# 50AN_DIGI.net
KiCad netlist of a schematic drawn in Altium Designer
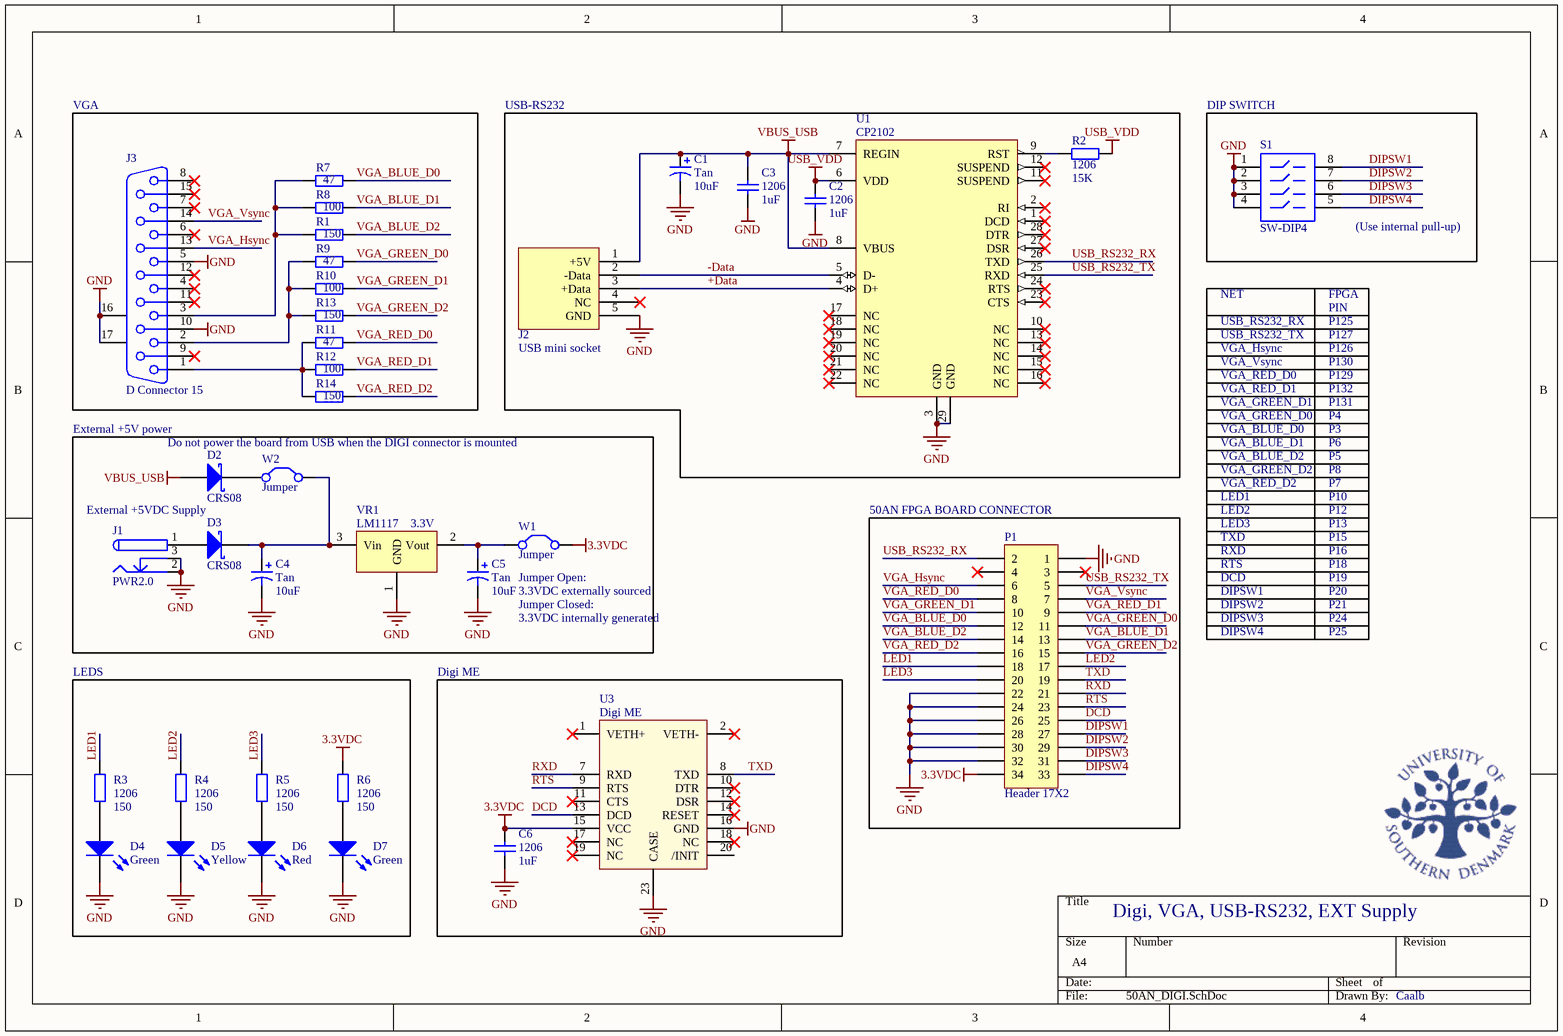
[diagram p0: 50AN_DIGI.SchDoc]

(export (version "E")
  (design (tool "Eeschema 10.0.6"))
  (components
    (comp (ref "C1")
      (value "Tan")
      (footprint "Tantal size A")
      (description "Polarized Capacitor (Radial)")
      (fields (field (name "ALTIUM_VALUE") "10uF") (field (name "PUBLISHER") "Altium Limited"))
      (libsource (lib "Miscellaneous Devices") (part "Cap Pol1"))
    )
    (comp (ref "C2")
      (value "1206")
      (footprint "1206C")
      (description "Capacitor")
      (fields (field (name "ALTIUM_VALUE") "1uF") (field (name "PUBLISHER") "Altium Limited"))
      (libsource (lib "Miscellaneous Devices") (part "Cap"))
    )
    (comp (ref "C3")
      (value "1206")
      (footprint "1206C")
      (description "Capacitor")
      (fields (field (name "ALTIUM_VALUE") "1uF") (field (name "PUBLISHER") "Altium Limited"))
      (libsource (lib "Miscellaneous Devices") (part "Cap"))
    )
    (comp (ref "C4")
      (value "Tan")
      (footprint "Tantal size A")
      (description "Polarized Capacitor (Radial)")
      (fields (field (name "ALTIUM_VALUE") "10uF") (field (name "PUBLISHER") "Altium Limited"))
      (libsource (lib "Miscellaneous Devices") (part "Cap Pol1"))
    )
    (comp (ref "C5")
      (value "Tan")
      (footprint "Tantal size A")
      (description "Polarized Capacitor (Radial)")
      (fields (field (name "ALTIUM_VALUE") "10uF") (field (name "PUBLISHER") "Altium Limited"))
      (libsource (lib "Miscellaneous Devices") (part "Cap Pol1"))
    )
    (comp (ref "C6")
      (value "1206")
      (footprint "1206C")
      (description "Capacitor")
      (fields (field (name "ALTIUM_VALUE") "1uF") (field (name "PUBLISHER") "Altium Limited"))
      (libsource (lib "Miscellaneous Devices") (part "Cap"))
    )
    (comp (ref "D2")
      (value "CRS08")
      (footprint "CRS08")
      (description "Schottky Rectifier")
      (fields (field (name "PUBLISHER") "Altium Limited"))
      (libsource (lib "Miscellaneous Devices") (part "Diode 11DQ03"))
    )
    (comp (ref "D3")
      (value "CRS08")
      (footprint "CRS08")
      (description "Schottky Rectifier")
      (fields (field (name "PUBLISHER") "Altium Limited"))
      (libsource (lib "Miscellaneous Devices") (part "Diode 11DQ03"))
    )
    (comp (ref "D4")
      (value "Green")
      (footprint "LED1206G")
      (fields (field (name "PUBLISHER") "Altium Limited"))
      (libsource (lib "Miscellaneous Devices") (part "LED0"))
    )
    (comp (ref "D5")
      (value "Yellow")
      (footprint "LED1206Y")
      (fields (field (name "PUBLISHER") "Altium Limited"))
      (libsource (lib "Miscellaneous Devices") (part "LED0"))
    )
    (comp (ref "D6")
      (value "Red")
      (footprint "LED1206R")
      (fields (field (name "PUBLISHER") "Altium Limited"))
      (libsource (lib "Miscellaneous Devices") (part "LED0"))
    )
    (comp (ref "D7")
      (value "Green")
      (footprint "LED1206G")
      (fields (field (name "PUBLISHER") "Altium Limited"))
      (libsource (lib "Miscellaneous Devices") (part "LED0"))
    )
    (comp (ref "J1")
      (value "PWR2.0")
      (footprint "DC FATN Ø2.0")
      (description "Low Voltage Power Supply Connector")
      (fields (field (name "PUBLISHER") "Altium Limited"))
      (libsource (lib "Miscellaneous Connectors") (part "PWR2.5"))
    )
    (comp (ref "J2")
      (value "USB mini socket")
      (footprint "Mini USB SMD F:1243250")
      (description "LUMBERG - 2486 01 - SOCKET, MINI, USB, B-TYPE, SMT")
      (fields (field (name "MANUFACTURER PART NUMBER") "2486 01") (field (name "MANUFACTURER") "LUMBERG"))
      (libsource (lib "DivLib") (part "USB mini socket"))
    )
    (comp (ref "J3")
      (value "D Connector 15")
      (footprint "HDSUB 15")
      (description "Receptacle Assembly, 15 Position, Right Angle")
      (fields (field (name "PUBLISHER") "Altium Limited"))
      (libsource (lib "Miscellaneous Connectors") (part "D Connector 15"))
    )
    (comp (ref "P1")
      (value "Header 17X2")
      (footprint "50AN HDR2X17")
      (description "Header, 17-Pin, Dual row")
      (fields (field (name "PUBLISHER") "Altium Limited"))
      (libsource (lib "Miscellaneous Connectors") (part "Header 17X2"))
    )
    (comp (ref "R1")
      (value "150")
      (footprint "1206R")
      (description "Resistor")
      (fields (field (name "Comment") "1206") (field (name "PUBLISHER") "Altium Limited"))
      (libsource (lib "Miscellaneous Devices") (part "Res2"))
    )
    (comp (ref "R2")
      (value "1206")
      (footprint "1206R")
      (description "Resistor")
      (fields (field (name "ALTIUM_VALUE") "15K") (field (name "PUBLISHER") "Altium Limited"))
      (libsource (lib "Miscellaneous Devices") (part "Res2"))
    )
    (comp (ref "R3")
      (value "1206")
      (footprint "1206R")
      (description "Resistor")
      (fields (field (name "ALTIUM_VALUE") "150") (field (name "PUBLISHER") "Altium Limited"))
      (libsource (lib "") (part "Res2_1"))
    )
    (comp (ref "R4")
      (value "1206")
      (footprint "1206R")
      (description "Resistor")
      (fields (field (name "ALTIUM_VALUE") "150") (field (name "PUBLISHER") "Altium Limited"))
      (libsource (lib "") (part "Res2_1"))
    )
    (comp (ref "R5")
      (value "1206")
      (footprint "1206R")
      (description "Resistor")
      (fields (field (name "ALTIUM_VALUE") "150") (field (name "PUBLISHER") "Altium Limited"))
      (libsource (lib "") (part "Res2_1"))
    )
    (comp (ref "R6")
      (value "1206")
      (footprint "1206R")
      (description "Resistor")
      (fields (field (name "ALTIUM_VALUE") "150") (field (name "PUBLISHER") "Altium Limited"))
      (libsource (lib "") (part "Res2_1"))
    )
    (comp (ref "R7")
      (value "47")
      (footprint "1206R")
      (description "Resistor")
      (fields (field (name "Comment") "1206") (field (name "PUBLISHER") "Altium Limited"))
      (libsource (lib "Miscellaneous Devices") (part "Res2"))
    )
    (comp (ref "R8")
      (value "100")
      (footprint "1206R")
      (description "Resistor")
      (fields (field (name "Comment") "1206") (field (name "PUBLISHER") "Altium Limited"))
      (libsource (lib "Miscellaneous Devices") (part "Res2"))
    )
    (comp (ref "R9")
      (value "47")
      (footprint "1206R")
      (description "Resistor")
      (fields (field (name "Comment") "1206") (field (name "PUBLISHER") "Altium Limited"))
      (libsource (lib "Miscellaneous Devices") (part "Res2"))
    )
    (comp (ref "R10")
      (value "100")
      (footprint "1206R")
      (description "Resistor")
      (fields (field (name "Comment") "1206") (field (name "PUBLISHER") "Altium Limited"))
      (libsource (lib "Miscellaneous Devices") (part "Res2"))
    )
    (comp (ref "R11")
      (value "47")
      (footprint "1206R")
      (description "Resistor")
      (fields (field (name "Comment") "1206") (field (name "PUBLISHER") "Altium Limited"))
      (libsource (lib "Miscellaneous Devices") (part "Res2"))
    )
    (comp (ref "R12")
      (value "100")
      (footprint "1206R")
      (description "Resistor")
      (fields (field (name "Comment") "1206") (field (name "PUBLISHER") "Altium Limited"))
      (libsource (lib "Miscellaneous Devices") (part "Res2"))
    )
    (comp (ref "R13")
      (value "150")
      (footprint "1206R")
      (description "Resistor")
      (fields (field (name "Comment") "1206") (field (name "PUBLISHER") "Altium Limited"))
      (libsource (lib "Miscellaneous Devices") (part "Res2"))
    )
    (comp (ref "R14")
      (value "150")
      (footprint "1206R")
      (description "Resistor")
      (fields (field (name "Comment") "1206") (field (name "PUBLISHER") "Altium Limited"))
      (libsource (lib "Miscellaneous Devices") (part "Res2"))
    )
    (comp (ref "S1")
      (value "SW-DIP4")
      (footprint "DIP SW 4")
      (description "DIP Switch")
      (fields (field (name "PUBLISHER") "Altium Limited"))
      (libsource (lib "Miscellaneous Devices") (part "SW-DIP4"))
    )
    (comp (ref "U1")
      (value "CP2102")
      (footprint "MLP-28")
      (description "IC USB-TO-UART BRIDGE 28MLP")
      (fields (field (name "MANUFACTURER") "Silicon Laboratories  Inc"))
      (libsource (lib "DivLib") (part "CP2102"))
    )
    (comp (ref "U3")
      (value "Digi ME")
      (footprint "Digi Connect ME")
      (description "Digi One ME connector")
      (libsource (lib "DivLib") (part "Digi ME"))
    )
    (comp (ref "VR1")
      (value "LM1117")
      (footprint "SOT-223")
      (description "NATIONAL SEMICONDUCTOR - LM1117IMP-3.3 - Linear Voltage Regulator IC")
      (fields (field (name "ALTIUM_VALUE") "3.3V") (field (name "MANUFACTURER PART NUMBER") "LM1117IMP-3.3"))
      (libsource (lib "DivLib") (part "LM1117"))
    )
    (comp (ref "W1")
      (value "Jumper")
      (footprint "HDR1X2")
      (description "Jumper Wire")
      (fields (field (name "PUBLISHER") "Altium Limited"))
      (libsource (lib "Miscellaneous Devices") (part "Jumper"))
    )
    (comp (ref "W2")
      (value "Jumper")
      (footprint "HDR1X2")
      (description "Jumper Wire")
      (fields (field (name "PUBLISHER") "Altium Limited"))
      (libsource (lib "Miscellaneous Devices") (part "Jumper"))
    )
  )
  (nets
    (net (code "1") (name "/+Data") (class "Default")
      (node (ref "J2") (pin "3") (pinfunction "+Data_3") (pintype "passive"))
      (node (ref "U1") (pin "4") (pinfunction "D+_4") (pintype "bidirectional"))
    )
    (net (code "2") (name "/-Data") (class "Default")
      (node (ref "J2") (pin "2") (pinfunction "-Data_2") (pintype "passive"))
      (node (ref "U1") (pin "5") (pinfunction "D-_5") (pintype "bidirectional"))
    )
    (net (code "3") (name "/DCD") (class "Default")
      (node (ref "P1") (pin "25") (pinfunction "25_25") (pintype "passive"))
      (node (ref "U3") (pin "13") (pinfunction "DCD_13") (pintype "power_in"))
    )
    (net (code "4") (name "/DIPSW1") (class "Default")
      (node (ref "P1") (pin "27") (pinfunction "27_27") (pintype "passive"))
      (node (ref "S1") (pin "8") (pinfunction "8_8") (pintype "passive"))
    )
    (net (code "5") (name "/DIPSW2") (class "Default")
      (node (ref "P1") (pin "29") (pinfunction "29_29") (pintype "passive"))
      (node (ref "S1") (pin "7") (pinfunction "7_7") (pintype "passive"))
    )
    (net (code "6") (name "/DIPSW3") (class "Default")
      (node (ref "P1") (pin "31") (pinfunction "31_31") (pintype "passive"))
      (node (ref "S1") (pin "6") (pinfunction "6_6") (pintype "passive"))
    )
    (net (code "7") (name "/DIPSW4") (class "Default")
      (node (ref "P1") (pin "33") (pinfunction "33_33") (pintype "passive"))
      (node (ref "S1") (pin "5") (pinfunction "5_5") (pintype "passive"))
    )
    (net (code "8") (name "/LED1") (class "Default")
      (node (ref "P1") (pin "18") (pinfunction "18_18") (pintype "passive"))
      (node (ref "R3") (pin "1") (pinfunction "1_1") (pintype "passive"))
    )
    (net (code "9") (name "/LED2") (class "Default")
      (node (ref "P1") (pin "17") (pinfunction "17_17") (pintype "passive"))
      (node (ref "R4") (pin "1") (pinfunction "1_1") (pintype "passive"))
    )
    (net (code "10") (name "/LED3") (class "Default")
      (node (ref "P1") (pin "20") (pinfunction "20_20") (pintype "passive"))
      (node (ref "R5") (pin "1") (pinfunction "1_1") (pintype "passive"))
    )
    (net (code "11") (name "/RTS") (class "Default")
      (node (ref "P1") (pin "23") (pinfunction "23_23") (pintype "passive"))
      (node (ref "U3") (pin "9") (pinfunction "RTS_9") (pintype "power_in"))
    )
    (net (code "12") (name "/RXD") (class "Default")
      (node (ref "P1") (pin "21") (pinfunction "21_21") (pintype "passive"))
      (node (ref "U3") (pin "7") (pinfunction "RXD_7") (pintype "power_in"))
    )
    (net (code "13") (name "/TXD") (class "Default")
      (node (ref "P1") (pin "19") (pinfunction "19_19") (pintype "passive"))
      (node (ref "U3") (pin "8") (pinfunction "TXD_8") (pintype "power_in"))
    )
    (net (code "14") (name "/USB_RS232_RX") (class "Default")
      (node (ref "P1") (pin "2") (pinfunction "2_2") (pintype "passive"))
      (node (ref "U1") (pin "26") (pinfunction "TXD_26") (pintype "output"))
    )
    (net (code "15") (name "/USB_RS232_TX") (class "Default")
      (node (ref "P1") (pin "5") (pinfunction "5_5") (pintype "passive"))
      (node (ref "U1") (pin "25") (pinfunction "RXD_25") (pintype "input"))
    )
    (net (code "16") (name "/VGA_BLUE_D0") (class "Default")
      (node (ref "P1") (pin "12") (pinfunction "12_12") (pintype "passive"))
      (node (ref "R7") (pin "1") (pinfunction "1_1") (pintype "passive"))
    )
    (net (code "17") (name "/VGA_BLUE_D1") (class "Default")
      (node (ref "P1") (pin "13") (pinfunction "13_13") (pintype "passive"))
      (node (ref "R8") (pin "1") (pinfunction "1_1") (pintype "passive"))
    )
    (net (code "18") (name "/VGA_BLUE_D2") (class "Default")
      (node (ref "P1") (pin "14") (pinfunction "14_14") (pintype "passive"))
      (node (ref "R1") (pin "1") (pinfunction "1_1") (pintype "passive"))
    )
    (net (code "19") (name "/VGA_GREEN_D0") (class "Default")
      (node (ref "P1") (pin "11") (pinfunction "11_11") (pintype "passive"))
      (node (ref "R9") (pin "1") (pinfunction "1_1") (pintype "passive"))
    )
    (net (code "20") (name "/VGA_GREEN_D1") (class "Default")
      (node (ref "P1") (pin "10") (pinfunction "10_10") (pintype "passive"))
      (node (ref "R10") (pin "1") (pinfunction "1_1") (pintype "passive"))
    )
    (net (code "21") (name "/VGA_GREEN_D2") (class "Default")
      (node (ref "P1") (pin "15") (pinfunction "15_15") (pintype "passive"))
      (node (ref "R13") (pin "1") (pinfunction "1_1") (pintype "passive"))
    )
    (net (code "22") (name "/VGA_Hsync") (class "Default")
      (node (ref "J3") (pin "13") (pinfunction "13_13") (pintype "passive"))
      (node (ref "P1") (pin "6") (pinfunction "6_6") (pintype "passive"))
    )
    (net (code "23") (name "/VGA_RED_D0") (class "Default")
      (node (ref "P1") (pin "8") (pinfunction "8_8") (pintype "passive"))
      (node (ref "R11") (pin "1") (pinfunction "1_1") (pintype "passive"))
    )
    (net (code "24") (name "/VGA_RED_D1") (class "Default")
      (node (ref "P1") (pin "9") (pinfunction "9_9") (pintype "passive"))
      (node (ref "R12") (pin "1") (pinfunction "1_1") (pintype "passive"))
    )
    (net (code "25") (name "/VGA_RED_D2") (class "Default")
      (node (ref "P1") (pin "16") (pinfunction "16_16") (pintype "passive"))
      (node (ref "R14") (pin "1") (pinfunction "1_1") (pintype "passive"))
    )
    (net (code "26") (name "/VGA_Vsync") (class "Default")
      (node (ref "J3") (pin "14") (pinfunction "14_14") (pintype "passive"))
      (node (ref "P1") (pin "7") (pinfunction "7_7") (pintype "passive"))
    )
    (net (code "27") (name "3.3VDC") (class "Default")
      (node (ref "C6") (pin "2") (pinfunction "2_2") (pintype "passive"))
      (node (ref "P1") (pin "34") (pinfunction "34_34") (pintype "passive"))
      (node (ref "R6") (pin "1") (pinfunction "1_1") (pintype "passive"))
      (node (ref "U3") (pin "15") (pinfunction "VCC_15") (pintype "power_in"))
      (node (ref "W1") (pin "2") (pinfunction "C2_2") (pintype "passive"))
    )
    (net (code "28") (name "GND") (class "Default")
      (node (ref "C1") (pin "2") (pinfunction "2_2") (pintype "passive"))
      (node (ref "C2") (pin "1") (pinfunction "1_1") (pintype "passive"))
      (node (ref "C3") (pin "1") (pinfunction "1_1") (pintype "passive"))
      (node (ref "C4") (pin "2") (pinfunction "2_2") (pintype "passive"))
      (node (ref "C5") (pin "2") (pinfunction "2_2") (pintype "passive"))
      (node (ref "C6") (pin "1") (pinfunction "1_1") (pintype "passive"))
      (node (ref "D4") (pin "2") (pinfunction "K_2") (pintype "passive"))
      (node (ref "D5") (pin "2") (pinfunction "K_2") (pintype "passive"))
      (node (ref "D6") (pin "2") (pinfunction "K_2") (pintype "passive"))
      (node (ref "D7") (pin "2") (pinfunction "K_2") (pintype "passive"))
      (node (ref "J1") (pin "2") (pinfunction "2_2") (pintype "power_in"))
      (node (ref "J1") (pin "3") (pinfunction "3_3") (pintype "power_in"))
      (node (ref "J2") (pin "5") (pinfunction "GND_5") (pintype "passive"))
      (node (ref "J3") (pin "10") (pinfunction "10_10") (pintype "passive"))
      (node (ref "J3") (pin "16") (pinfunction "MH1_16") (pintype "passive"))
      (node (ref "J3") (pin "17") (pinfunction "MH2_17") (pintype "passive"))
      (node (ref "J3") (pin "5") (pinfunction "5_5") (pintype "passive"))
      (node (ref "P1") (pin "1") (pinfunction "1_1") (pintype "passive"))
      (node (ref "P1") (pin "22") (pinfunction "22_22") (pintype "passive"))
      (node (ref "P1") (pin "24") (pinfunction "24_24") (pintype "passive"))
      (node (ref "P1") (pin "26") (pinfunction "26_26") (pintype "passive"))
      (node (ref "P1") (pin "28") (pinfunction "28_28") (pintype "passive"))
      (node (ref "P1") (pin "30") (pinfunction "30_30") (pintype "passive"))
      (node (ref "P1") (pin "32") (pinfunction "32_32") (pintype "passive"))
      (node (ref "S1") (pin "1") (pinfunction "1_1") (pintype "passive"))
      (node (ref "S1") (pin "2") (pinfunction "2_2") (pintype "passive"))
      (node (ref "S1") (pin "3") (pinfunction "3_3") (pintype "passive"))
      (node (ref "S1") (pin "4") (pinfunction "4_4") (pintype "passive"))
      (node (ref "U1") (pin "29") (pinfunction "GND_29") (pintype "power_in"))
      (node (ref "U1") (pin "3") (pinfunction "GND_3") (pintype "power_in"))
      (node (ref "U3") (pin "16") (pinfunction "GND_16") (pintype "power_in"))
      (node (ref "U3") (pin "23") (pinfunction "CASE_23") (pintype "power_in"))
      (node (ref "VR1") (pin "1") (pinfunction "GND_1") (pintype "power_in"))
    )
    (net (code "29") (name "Net-(D2-K)") (class "Default")
      (node (ref "D2") (pin "2") (pinfunction "K_2") (pintype "passive"))
      (node (ref "W2") (pin "1") (pinfunction "C1_1") (pintype "passive"))
    )
    (net (code "30") (name "Net-(D3-A)") (class "Default")
      (node (ref "D3") (pin "1") (pinfunction "A_1") (pintype "passive"))
      (node (ref "J1") (pin "1") (pinfunction "1_1") (pintype "power_in"))
    )
    (net (code "31") (name "Net-(D3-K)") (class "Default")
      (node (ref "C4") (pin "1") (pinfunction "1_1") (pintype "passive"))
      (node (ref "D3") (pin "2") (pinfunction "K_2") (pintype "passive"))
      (node (ref "VR1") (pin "3") (pinfunction "Vin_3") (pintype "power_in"))
      (node (ref "W2") (pin "2") (pinfunction "C2_2") (pintype "passive"))
    )
    (net (code "32") (name "Net-(D4-A)") (class "Default")
      (node (ref "D4") (pin "1") (pinfunction "A_1") (pintype "passive"))
      (node (ref "R3") (pin "2") (pinfunction "2_2") (pintype "passive"))
    )
    (net (code "33") (name "Net-(D5-A)") (class "Default")
      (node (ref "D5") (pin "1") (pinfunction "A_1") (pintype "passive"))
      (node (ref "R4") (pin "2") (pinfunction "2_2") (pintype "passive"))
    )
    (net (code "34") (name "Net-(D6-A)") (class "Default")
      (node (ref "D6") (pin "1") (pinfunction "A_1") (pintype "passive"))
      (node (ref "R5") (pin "2") (pinfunction "2_2") (pintype "passive"))
    )
    (net (code "35") (name "Net-(D7-A)") (class "Default")
      (node (ref "D7") (pin "1") (pinfunction "A_1") (pintype "passive"))
      (node (ref "R6") (pin "2") (pinfunction "2_2") (pintype "passive"))
    )
    (net (code "36") (name "Net-(J3-Pad1)") (class "Default")
      (node (ref "J3") (pin "1") (pinfunction "1_1") (pintype "passive"))
      (node (ref "R11") (pin "2") (pinfunction "2_2") (pintype "passive"))
      (node (ref "R12") (pin "2") (pinfunction "2_2") (pintype "passive"))
      (node (ref "R14") (pin "2") (pinfunction "2_2") (pintype "passive"))
    )
    (net (code "37") (name "Net-(J3-Pad2)") (class "Default")
      (node (ref "J3") (pin "2") (pinfunction "2_2") (pintype "passive"))
      (node (ref "R10") (pin "2") (pinfunction "2_2") (pintype "passive"))
      (node (ref "R13") (pin "2") (pinfunction "2_2") (pintype "passive"))
      (node (ref "R9") (pin "2") (pinfunction "2_2") (pintype "passive"))
    )
    (net (code "38") (name "Net-(J3-Pad3)") (class "Default")
      (node (ref "J3") (pin "3") (pinfunction "3_3") (pintype "passive"))
      (node (ref "R1") (pin "2") (pinfunction "2_2") (pintype "passive"))
      (node (ref "R7") (pin "2") (pinfunction "2_2") (pintype "passive"))
      (node (ref "R8") (pin "2") (pinfunction "2_2") (pintype "passive"))
    )
    (net (code "39") (name "Net-(U1-RST)") (class "Default")
      (node (ref "R2") (pin "2") (pinfunction "2_2") (pintype "passive"))
      (node (ref "U1") (pin "9") (pinfunction "RST_9") (pintype "open_collector"))
    )
    (net (code "40") (name "Net-(VR1-Vout)") (class "Default")
      (node (ref "C5") (pin "1") (pinfunction "1_1") (pintype "passive"))
      (node (ref "VR1") (pin "2") (pinfunction "Vout_2") (pintype "power_in"))
      (node (ref "W1") (pin "1") (pinfunction "C1_1") (pintype "passive"))
    )
    (net (code "41") (name "USB_VDD") (class "Default")
      (node (ref "C2") (pin "2") (pinfunction "2_2") (pintype "passive"))
      (node (ref "R2") (pin "1") (pinfunction "1_1") (pintype "passive"))
      (node (ref "U1") (pin "6") (pinfunction "VDD_6") (pintype "power_in"))
    )
    (net (code "42") (name "VBUS_USB") (class "Default")
      (node (ref "C1") (pin "1") (pinfunction "1_1") (pintype "passive"))
      (node (ref "C3") (pin "2") (pinfunction "2_2") (pintype "passive"))
      (node (ref "D2") (pin "1") (pinfunction "A_1") (pintype "passive"))
      (node (ref "J2") (pin "1") (pinfunction "+5V_1") (pintype "passive"))
      (node (ref "U1") (pin "7") (pinfunction "REGIN_7") (pintype "power_in"))
      (node (ref "U1") (pin "8") (pinfunction "VBUS_8") (pintype "power_in"))
    )
    (net (code "43") (name "unconnected-(J2-NC-Pad4)") (class "Default")
      (node (ref "J2") (pin "4") (pinfunction "NC_4") (pintype "passive+no_connect"))
    )
    (net (code "44") (name "unconnected-(J3-Pad4)") (class "Default")
      (node (ref "J3") (pin "4") (pinfunction "4_4") (pintype "passive+no_connect"))
    )
    (net (code "45") (name "unconnected-(J3-Pad6)") (class "Default")
      (node (ref "J3") (pin "6") (pinfunction "6_6") (pintype "passive+no_connect"))
    )
    (net (code "46") (name "unconnected-(J3-Pad7)") (class "Default")
      (node (ref "J3") (pin "7") (pinfunction "7_7") (pintype "passive+no_connect"))
    )
    (net (code "47") (name "unconnected-(J3-Pad8)") (class "Default")
      (node (ref "J3") (pin "8") (pinfunction "8_8") (pintype "passive+no_connect"))
    )
    (net (code "48") (name "unconnected-(J3-Pad9)") (class "Default")
      (node (ref "J3") (pin "9") (pinfunction "9_9") (pintype "passive+no_connect"))
    )
    (net (code "49") (name "unconnected-(J3-Pad11)") (class "Default")
      (node (ref "J3") (pin "11") (pinfunction "11_11") (pintype "passive+no_connect"))
    )
    (net (code "50") (name "unconnected-(J3-Pad12)") (class "Default")
      (node (ref "J3") (pin "12") (pinfunction "12_12") (pintype "passive+no_connect"))
    )
    (net (code "51") (name "unconnected-(J3-Pad15)") (class "Default")
      (node (ref "J3") (pin "15") (pinfunction "15_15") (pintype "passive+no_connect"))
    )
    (net (code "52") (name "unconnected-(P1-Pad3)") (class "Default")
      (node (ref "P1") (pin "3") (pinfunction "3_3") (pintype "passive+no_connect"))
    )
    (net (code "53") (name "unconnected-(P1-Pad4)") (class "Default")
      (node (ref "P1") (pin "4") (pinfunction "4_4") (pintype "passive+no_connect"))
    )
    (net (code "54") (name "unconnected-(U1-CTS-Pad23)") (class "Default")
      (node (ref "U1") (pin "23") (pinfunction "CTS_23") (pintype "input+no_connect"))
    )
    (net (code "55") (name "unconnected-(U1-DCD-Pad1)") (class "Default")
      (node (ref "U1") (pin "1") (pinfunction "DCD_1") (pintype "input+no_connect"))
    )
    (net (code "56") (name "unconnected-(U1-DSR-Pad27)") (class "Default")
      (node (ref "U1") (pin "27") (pinfunction "DSR_27") (pintype "input+no_connect"))
    )
    (net (code "57") (name "unconnected-(U1-DTR-Pad28)") (class "Default")
      (node (ref "U1") (pin "28") (pinfunction "DTR_28") (pintype "output+no_connect"))
    )
    (net (code "58") (name "unconnected-(U1-NC-Pad10)") (class "Default")
      (node (ref "U1") (pin "10") (pinfunction "NC_10") (pintype "power_in+no_connect"))
    )
    (net (code "59") (name "unconnected-(U1-NC-Pad13)") (class "Default")
      (node (ref "U1") (pin "13") (pinfunction "NC_13") (pintype "power_in+no_connect"))
    )
    (net (code "60") (name "unconnected-(U1-NC-Pad14)") (class "Default")
      (node (ref "U1") (pin "14") (pinfunction "NC_14") (pintype "power_in+no_connect"))
    )
    (net (code "61") (name "unconnected-(U1-NC-Pad15)") (class "Default")
      (node (ref "U1") (pin "15") (pinfunction "NC_15") (pintype "power_in+no_connect"))
    )
    (net (code "62") (name "unconnected-(U1-NC-Pad16)") (class "Default")
      (node (ref "U1") (pin "16") (pinfunction "NC_16") (pintype "power_in+no_connect"))
    )
    (net (code "63") (name "unconnected-(U1-NC-Pad17)") (class "Default")
      (node (ref "U1") (pin "17") (pinfunction "NC_17") (pintype "power_in+no_connect"))
    )
    (net (code "64") (name "unconnected-(U1-NC-Pad18)") (class "Default")
      (node (ref "U1") (pin "18") (pinfunction "NC_18") (pintype "power_in+no_connect"))
    )
    (net (code "65") (name "unconnected-(U1-NC-Pad19)") (class "Default")
      (node (ref "U1") (pin "19") (pinfunction "NC_19") (pintype "power_in+no_connect"))
    )
    (net (code "66") (name "unconnected-(U1-NC-Pad20)") (class "Default")
      (node (ref "U1") (pin "20") (pinfunction "NC_20") (pintype "power_in+no_connect"))
    )
    (net (code "67") (name "unconnected-(U1-NC-Pad21)") (class "Default")
      (node (ref "U1") (pin "21") (pinfunction "NC_21") (pintype "power_in+no_connect"))
    )
    (net (code "68") (name "unconnected-(U1-NC-Pad22)") (class "Default")
      (node (ref "U1") (pin "22") (pinfunction "NC_22") (pintype "power_in+no_connect"))
    )
    (net (code "69") (name "unconnected-(U1-RI-Pad2)") (class "Default")
      (node (ref "U1") (pin "2") (pinfunction "RI_2") (pintype "input+no_connect"))
    )
    (net (code "70") (name "unconnected-(U1-RTS-Pad24)") (class "Default")
      (node (ref "U1") (pin "24") (pinfunction "RTS_24") (pintype "output+no_connect"))
    )
    (net (code "71") (name "unconnected-(U1-SUSPEND-Pad11)") (class "Default")
      (node (ref "U1") (pin "11") (pinfunction "SUSPEND_11") (pintype "output+no_connect"))
    )
    (net (code "72") (name "unconnected-(U1-SUSPEND-Pad12)") (class "Default")
      (node (ref "U1") (pin "12") (pinfunction "SUSPEND_12") (pintype "output+no_connect"))
    )
    (net (code "73") (name "unconnected-(U3-CTS-Pad11)") (class "Default")
      (node (ref "U3") (pin "11") (pinfunction "CTS_11") (pintype "power_in+no_connect"))
    )
    (net (code "74") (name "unconnected-(U3-DSR-Pad12)") (class "Default")
      (node (ref "U3") (pin "12") (pinfunction "DSR_12") (pintype "power_in+no_connect"))
    )
    (net (code "75") (name "unconnected-(U3-DTR-Pad10)") (class "Default")
      (node (ref "U3") (pin "10") (pinfunction "DTR_10") (pintype "power_in+no_connect"))
    )
    (net (code "76") (name "unconnected-(U3-NC-Pad17)") (class "Default")
      (node (ref "U3") (pin "17") (pinfunction "NC_17") (pintype "power_in+no_connect"))
    )
    (net (code "77") (name "unconnected-(U3-NC-Pad18)") (class "Default")
      (node (ref "U3") (pin "18") (pinfunction "NC_18") (pintype "power_in+no_connect"))
    )
    (net (code "78") (name "unconnected-(U3-NC-Pad19)") (class "Default")
      (node (ref "U3") (pin "19") (pinfunction "NC_19") (pintype "power_in+no_connect"))
    )
    (net (code "79") (name "unconnected-(U3-RESET-Pad14)") (class "Default")
      (node (ref "U3") (pin "14") (pinfunction "RESET_14") (pintype "power_in+no_connect"))
    )
    (net (code "80") (name "unconnected-(U3-VETH+-Pad1)") (class "Default")
      (node (ref "U3") (pin "1") (pinfunction "VETH+_1") (pintype "power_in+no_connect"))
    )
    (net (code "81") (name "unconnected-(U3-VETH--Pad2)") (class "Default")
      (node (ref "U3") (pin "2") (pinfunction "VETH-_2") (pintype "power_in+no_connect"))
    )
    (net (code "82") (name "unconnected-(U3-{slash}INIT-Pad20)") (class "Default")
      (node (ref "U3") (pin "20") (pinfunction "/INIT_20") (pintype "power_in"))
    )
  )
)
